# mainboard_rs485_v1_2.net
KiCad netlist of a schematic drawn in Altium Designer
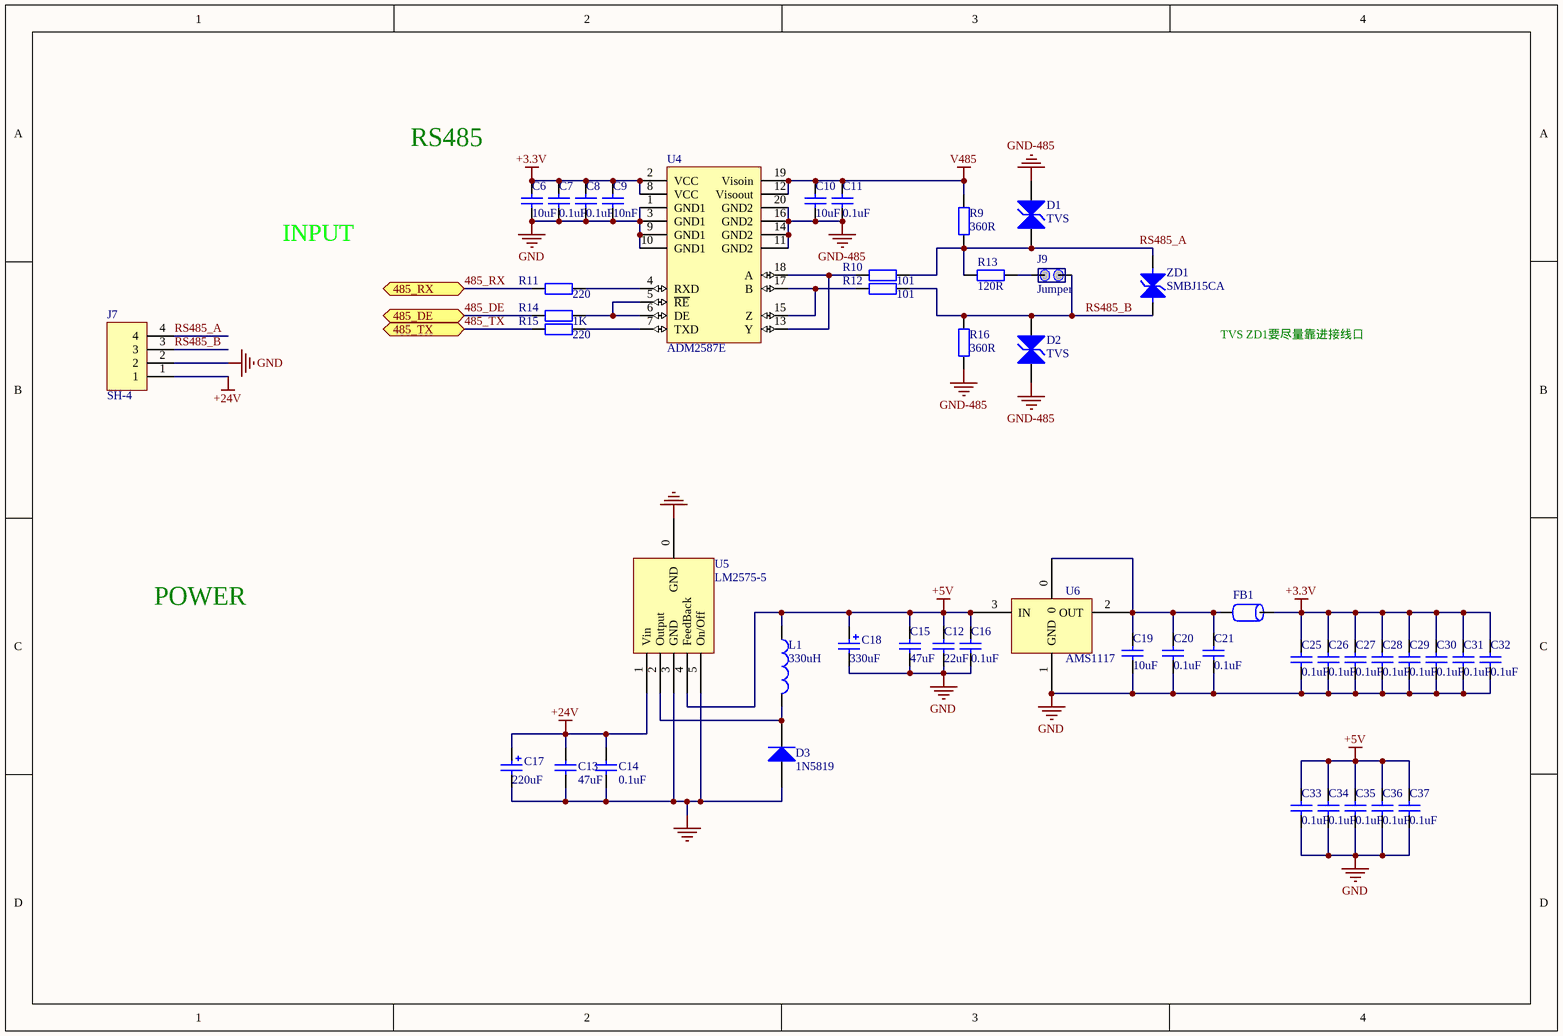
[diagram p0: mainboard_rs485.v1.2.SchDoc]

(export (version "E")
  (design (tool "Eeschema 10.0.6"))
  (components
    (comp (ref "C6")
      (value "10uF")
      (footprint "0805")
      (description "Capacitor")
      (fields (field (name "PUBLISHER") "Altium Limited"))
      (libsource (lib "TIAN's Schlib") (part "Cap"))
    )
    (comp (ref "C7")
      (value "0.1uF")
      (footprint "0805")
      (description "Capacitor")
      (fields (field (name "PUBLISHER") "Altium Limited"))
      (libsource (lib "TIAN's Schlib") (part "Cap"))
    )
    (comp (ref "C8")
      (value "0.1uF")
      (footprint "0805")
      (description "Capacitor")
      (fields (field (name "PUBLISHER") "Altium Limited"))
      (libsource (lib "TIAN's Schlib") (part "Cap"))
    )
    (comp (ref "C9")
      (value "10nF")
      (footprint "0805")
      (description "Capacitor")
      (fields (field (name "PUBLISHER") "Altium Limited"))
      (libsource (lib "TIAN's Schlib") (part "Cap"))
    )
    (comp (ref "C10")
      (value "10uF")
      (footprint "0805")
      (description "Capacitor")
      (fields (field (name "PUBLISHER") "Altium Limited"))
      (libsource (lib "TIAN's Schlib") (part "Cap"))
    )
    (comp (ref "C11")
      (value "0.1uF")
      (footprint "0805")
      (description "Capacitor")
      (fields (field (name "PUBLISHER") "Altium Limited"))
      (libsource (lib "TIAN's Schlib") (part "Cap"))
    )
    (comp (ref "C12") (value "22uF") (footprint "1206") (libsource (lib "Componet") (part "Cap0805")))
    (comp (ref "C13")
      (value "47uF")
      (footprint "1812")
      (description "Capacitor")
      (fields (field (name "PUBLISHER") "Altium Limited"))
      (libsource (lib "Miscellaneous Devices") (part "Cap"))
    )
    (comp (ref "C14")
      (value "0.1uF")
      (footprint "0805")
      (description "Capacitor")
      (fields (field (name "PUBLISHER") "Altium Limited"))
      (libsource (lib "Miscellaneous Devices") (part "Cap"))
    )
    (comp (ref "C15") (value "47uF") (footprint "1812") (libsource (lib "Componet") (part "Cap0805")))
    (comp (ref "C16") (value "0.1uF") (footprint "0805") (libsource (lib "Componet") (part "Cap0805")))
    (comp (ref "C17")
      (value "220uF")
      (footprint "CAP-5mm")
      (description "Polarized Capacitor (Radial)")
      (fields (field (name "PUBLISHER") "Altium Limited"))
      (libsource (lib "Miscellaneous Devices") (part "Cap Pol1"))
    )
    (comp (ref "C18")
      (value "330uF")
      (footprint "CAP-5mm")
      (description "Polarized Capacitor (Radial)")
      (fields (field (name "PUBLISHER") "Altium Limited"))
      (libsource (lib "Miscellaneous Devices") (part "Cap Pol1"))
    )
    (comp (ref "C19") (value "10uF") (footprint "0805") (libsource (lib "Componet") (part "Cap0805")))
    (comp (ref "C20") (value "0.1uF") (footprint "0805") (libsource (lib "Componet") (part "Cap0805")))
    (comp (ref "C21") (value "0.1uF") (footprint "0805") (libsource (lib "Componet") (part "Cap0805")))
    (comp (ref "C25") (value "0.1uF") (footprint "0805") (libsource (lib "Componet") (part "Cap0805")))
    (comp (ref "C26") (value "0.1uF") (footprint "0805") (libsource (lib "Componet") (part "Cap0805")))
    (comp (ref "C27") (value "0.1uF") (footprint "0805") (libsource (lib "Componet") (part "Cap0805")))
    (comp (ref "C28") (value "0.1uF") (footprint "0805") (libsource (lib "Componet") (part "Cap0805")))
    (comp (ref "C29") (value "0.1uF") (footprint "0805") (libsource (lib "Componet") (part "Cap0805")))
    (comp (ref "C30") (value "0.1uF") (footprint "0805") (libsource (lib "Componet") (part "Cap0805")))
    (comp (ref "C31") (value "0.1uF") (footprint "0805") (libsource (lib "Componet") (part "Cap0805")))
    (comp (ref "C32") (value "0.1uF") (footprint "0805") (libsource (lib "Componet") (part "Cap0805")))
    (comp (ref "C33") (value "0.1uF") (footprint "0805") (libsource (lib "Componet") (part "Cap0805")))
    (comp (ref "C34") (value "0.1uF") (footprint "0805") (libsource (lib "Componet") (part "Cap0805")))
    (comp (ref "C35") (value "0.1uF") (footprint "0805") (libsource (lib "Componet") (part "Cap0805")))
    (comp (ref "C36") (value "0.1uF") (footprint "0805") (libsource (lib "Componet") (part "Cap0805")))
    (comp (ref "C37") (value "0.1uF") (footprint "0805") (libsource (lib "Componet") (part "Cap0805")))
    (comp (ref "D1")
      (value "TVS")
      (footprint "SMBJ_DO-214")
      (fields (field (name "PUBLISHER") "Altium Limited"))
      (libsource (lib "TIAN's Schlib") (part "TVS"))
    )
    (comp (ref "D2")
      (value "TVS")
      (footprint "SMBJ_DO-214")
      (fields (field (name "PUBLISHER") "Altium Limited"))
      (libsource (lib "TIAN's Schlib") (part "TVS"))
    )
    (comp (ref "D3")
      (value "1N5819")
      (footprint "Diode_TP2")
      (description "High Conductance Fast Diode")
      (fields (field (name "PUBLISHER") "Altium Limited"))
      (libsource (lib "Miscellaneous Devices") (part "Diode 1N4148"))
    )
    (comp (ref "FB1") (value "FERRITE") (footprint "0805") (libsource (lib "Connector") (part "FERRITE")))
    (comp (ref "J7") (value "SH-4") (footprint "PWR") (libsource (lib "Connector") (part "SH-4")))
    (comp (ref "J9") (value "Jumper") (footprint "J254-2") (libsource (lib "Connector") (part "Jumper")))
    (comp (ref "L1")
      (value "330uH")
      (footprint "Inductance")
      (description "Inductor")
      (fields (field (name "PUBLISHER") "Altium Limited"))
      (libsource (lib "Miscellaneous Devices") (part "Inductor"))
    )
    (comp (ref "R9")
      (value "360R")
      (footprint "0805")
      (description "Resistor")
      (fields (field (name "PUBLISHER") "Altium Limited"))
      (libsource (lib "TIAN's Schlib") (part "Res2"))
    )
    (comp (ref "R10")
      (value "101")
      (footprint "0805")
      (description "Resistor")
      (fields (field (name "PUBLISHER") "Altium Limited"))
      (libsource (lib "") (part "Res2_1"))
    )
    (comp (ref "R11")
      (value "220")
      (footprint "0805")
      (description "Resistor")
      (fields (field (name "PUBLISHER") "Altium Limited"))
      (libsource (lib "TIAN's Schlib") (part "Res2"))
    )
    (comp (ref "R12")
      (value "101")
      (footprint "0805")
      (description "Resistor")
      (fields (field (name "PUBLISHER") "Altium Limited"))
      (libsource (lib "") (part "Res2_1"))
    )
    (comp (ref "R13")
      (value "120R")
      (footprint "0805")
      (description "Resistor")
      (fields (field (name "PUBLISHER") "Altium Limited"))
      (libsource (lib "") (part "Res2_2"))
    )
    (comp (ref "R14")
      (value "1K")
      (footprint "0805")
      (description "Resistor")
      (fields (field (name "PUBLISHER") "Altium Limited"))
      (libsource (lib "TIAN's Schlib") (part "Res2"))
    )
    (comp (ref "R15")
      (value "220")
      (footprint "0805")
      (description "Resistor")
      (fields (field (name "PUBLISHER") "Altium Limited"))
      (libsource (lib "TIAN's Schlib") (part "Res2"))
    )
    (comp (ref "R16")
      (value "360R")
      (footprint "0805")
      (description "Resistor")
      (fields (field (name "PUBLISHER") "Altium Limited"))
      (libsource (lib "TIAN's Schlib") (part "Res2"))
    )
    (comp (ref "U4")
      (value "ADM2587E")
      (footprint "SOIC_W_20")
      (description "isolated DC-DC RS485")
      (libsource (lib "TIAN's Schlib") (part "ADM2587E"))
    )
    (comp (ref "U5") (value "LM2575-5") (footprint "TO-263") (libsource (lib "Leon") (part "LM25XX")))
    (comp (ref "U6") (value "AMS1117") (footprint "TO-223") (libsource (lib "Chip") (part "AMS1117")))
    (comp (ref "ZD1")
      (value "SMBJ15CA")
      (footprint "DO-214AA/SMB")
      (description "瞬态抑制二极管")
      (libsource (lib "ALARM") (part "TVS"))
    )
  )
  (nets
    (net (code "1") (name "+3.3V") (class "Default")
      (node (ref "C25") (pin "2") (pinfunction "2_2") (pintype "passive"))
      (node (ref "C26") (pin "2") (pinfunction "2_2") (pintype "passive"))
      (node (ref "C27") (pin "2") (pinfunction "2_2") (pintype "passive"))
      (node (ref "C28") (pin "2") (pinfunction "2_2") (pintype "passive"))
      (node (ref "C29") (pin "2") (pinfunction "2_2") (pintype "passive"))
      (node (ref "C30") (pin "2") (pinfunction "2_2") (pintype "passive"))
      (node (ref "C31") (pin "2") (pinfunction "2_2") (pintype "passive"))
      (node (ref "C32") (pin "2") (pinfunction "2_2") (pintype "passive"))
      (node (ref "C6") (pin "2") (pinfunction "2_2") (pintype "passive"))
      (node (ref "C7") (pin "2") (pinfunction "2_2") (pintype "passive"))
      (node (ref "C8") (pin "2") (pinfunction "2_2") (pintype "passive"))
      (node (ref "C9") (pin "2") (pinfunction "2_2") (pintype "passive"))
      (node (ref "FB1") (pin "2") (pinfunction "2_2") (pintype "passive"))
      (node (ref "U4") (pin "2") (pinfunction "VCC_2") (pintype "passive"))
      (node (ref "U4") (pin "8") (pinfunction "VCC_8") (pintype "passive"))
    )
    (net (code "2") (name "+5V") (class "Default")
      (node (ref "C12") (pin "2") (pinfunction "2_2") (pintype "passive"))
      (node (ref "C15") (pin "2") (pinfunction "2_2") (pintype "passive"))
      (node (ref "C16") (pin "2") (pinfunction "2_2") (pintype "passive"))
      (node (ref "C18") (pin "1") (pinfunction "1_1") (pintype "passive"))
      (node (ref "C33") (pin "2") (pinfunction "2_2") (pintype "passive"))
      (node (ref "C34") (pin "2") (pinfunction "2_2") (pintype "passive"))
      (node (ref "C35") (pin "2") (pinfunction "2_2") (pintype "passive"))
      (node (ref "C36") (pin "2") (pinfunction "2_2") (pintype "passive"))
      (node (ref "C37") (pin "2") (pinfunction "2_2") (pintype "passive"))
      (node (ref "L1") (pin "1") (pinfunction "1_1") (pintype "passive"))
      (node (ref "U5") (pin "4") (pinfunction "FeedBack_4") (pintype "passive"))
      (node (ref "U6") (pin "3") (pinfunction "IN_3") (pintype "passive"))
    )
    (net (code "3") (name "+24V") (class "Default")
      (node (ref "C13") (pin "2") (pinfunction "2_2") (pintype "passive"))
      (node (ref "C14") (pin "2") (pinfunction "2_2") (pintype "passive"))
      (node (ref "C17") (pin "1") (pinfunction "1_1") (pintype "passive"))
      (node (ref "J7") (pin "1") (pinfunction "1_1") (pintype "passive"))
      (node (ref "U5") (pin "1") (pinfunction "Vin_1") (pintype "passive"))
    )
    (net (code "4") (name "/485_DE") (class "Default")
      (node (ref "R14") (pin "1") (pinfunction "1_1") (pintype "passive"))
    )
    (net (code "5") (name "/485_RX") (class "Default")
      (node (ref "R11") (pin "1") (pinfunction "1_1") (pintype "passive"))
    )
    (net (code "6") (name "/485_TX") (class "Default")
      (node (ref "R15") (pin "1") (pinfunction "1_1") (pintype "passive"))
    )
    (net (code "7") (name "/RS485_A") (class "Default")
      (node (ref "D1") (pin "2") (pinfunction "K_2") (pintype "passive"))
      (node (ref "J7") (pin "4") (pinfunction "4_4") (pintype "passive"))
      (node (ref "R10") (pin "2") (pinfunction "2_2") (pintype "passive"))
      (node (ref "R13") (pin "2") (pinfunction "2_2") (pintype "passive"))
      (node (ref "R9") (pin "1") (pinfunction "1_1") (pintype "passive"))
      (node (ref "ZD1") (pin "1") (pinfunction "1_1") (pintype "passive"))
    )
    (net (code "8") (name "/RS485_B") (class "Default")
      (node (ref "D2") (pin "2") (pinfunction "K_2") (pintype "passive"))
      (node (ref "J7") (pin "3") (pinfunction "3_3") (pintype "passive"))
      (node (ref "J9") (pin "1") (pinfunction "1_1") (pintype "passive"))
      (node (ref "R12") (pin "2") (pinfunction "2_2") (pintype "passive"))
      (node (ref "R16") (pin "2") (pinfunction "2_2") (pintype "passive"))
      (node (ref "ZD1") (pin "2") (pinfunction "2_2") (pintype "passive"))
    )
    (net (code "9") (name "GND") (class "Default")
      (node (ref "C12") (pin "1") (pinfunction "1_1") (pintype "passive"))
      (node (ref "C13") (pin "1") (pinfunction "1_1") (pintype "passive"))
      (node (ref "C14") (pin "1") (pinfunction "1_1") (pintype "passive"))
      (node (ref "C15") (pin "1") (pinfunction "1_1") (pintype "passive"))
      (node (ref "C16") (pin "1") (pinfunction "1_1") (pintype "passive"))
      (node (ref "C17") (pin "2") (pinfunction "2_2") (pintype "passive"))
      (node (ref "C18") (pin "2") (pinfunction "2_2") (pintype "passive"))
      (node (ref "C19") (pin "1") (pinfunction "1_1") (pintype "passive"))
      (node (ref "C20") (pin "1") (pinfunction "1_1") (pintype "passive"))
      (node (ref "C21") (pin "1") (pinfunction "1_1") (pintype "passive"))
      (node (ref "C25") (pin "1") (pinfunction "1_1") (pintype "passive"))
      (node (ref "C26") (pin "1") (pinfunction "1_1") (pintype "passive"))
      (node (ref "C27") (pin "1") (pinfunction "1_1") (pintype "passive"))
      (node (ref "C28") (pin "1") (pinfunction "1_1") (pintype "passive"))
      (node (ref "C29") (pin "1") (pinfunction "1_1") (pintype "passive"))
      (node (ref "C30") (pin "1") (pinfunction "1_1") (pintype "passive"))
      (node (ref "C31") (pin "1") (pinfunction "1_1") (pintype "passive"))
      (node (ref "C32") (pin "1") (pinfunction "1_1") (pintype "passive"))
      (node (ref "C33") (pin "1") (pinfunction "1_1") (pintype "passive"))
      (node (ref "C34") (pin "1") (pinfunction "1_1") (pintype "passive"))
      (node (ref "C35") (pin "1") (pinfunction "1_1") (pintype "passive"))
      (node (ref "C36") (pin "1") (pinfunction "1_1") (pintype "passive"))
      (node (ref "C37") (pin "1") (pinfunction "1_1") (pintype "passive"))
      (node (ref "C6") (pin "1") (pinfunction "1_1") (pintype "passive"))
      (node (ref "C7") (pin "1") (pinfunction "1_1") (pintype "passive"))
      (node (ref "C8") (pin "1") (pinfunction "1_1") (pintype "passive"))
      (node (ref "C9") (pin "1") (pinfunction "1_1") (pintype "passive"))
      (node (ref "D3") (pin "1") (pinfunction "A_1") (pintype "passive"))
      (node (ref "J7") (pin "2") (pinfunction "2_2") (pintype "passive"))
      (node (ref "U4") (pin "1") (pinfunction "GND1_1") (pintype "passive"))
      (node (ref "U4") (pin "10") (pinfunction "GND1_10") (pintype "passive"))
      (node (ref "U4") (pin "3") (pinfunction "GND1_3") (pintype "passive"))
      (node (ref "U4") (pin "9") (pinfunction "GND1_9") (pintype "passive"))
      (node (ref "U5") (pin "0") (pinfunction "GND_0") (pintype "passive"))
      (node (ref "U5") (pin "3") (pinfunction "GND_3") (pintype "passive"))
      (node (ref "U5") (pin "5") (pinfunction "On/Off_5") (pintype "passive"))
      (node (ref "U6") (pin "1") (pinfunction "GND_1") (pintype "passive"))
    )
    (net (code "10") (name "GND-485") (class "Default")
      (node (ref "C10") (pin "1") (pinfunction "1_1") (pintype "passive"))
      (node (ref "C11") (pin "1") (pinfunction "1_1") (pintype "passive"))
      (node (ref "D1") (pin "1") (pinfunction "A_1") (pintype "passive"))
      (node (ref "D2") (pin "1") (pinfunction "A_1") (pintype "passive"))
      (node (ref "R16") (pin "1") (pinfunction "1_1") (pintype "passive"))
      (node (ref "U4") (pin "11") (pinfunction "GND2_11") (pintype "passive"))
      (node (ref "U4") (pin "14") (pinfunction "GND2_14") (pintype "passive"))
      (node (ref "U4") (pin "16") (pinfunction "GND2_16") (pintype "passive"))
      (node (ref "U4") (pin "20") (pinfunction "GND2_20") (pintype "passive"))
    )
    (net (code "11") (name "Net-(D3-K)") (class "Default")
      (node (ref "D3") (pin "2") (pinfunction "K_2") (pintype "passive"))
      (node (ref "L1") (pin "2") (pinfunction "2_2") (pintype "passive"))
      (node (ref "U5") (pin "2") (pinfunction "Output_2") (pintype "passive"))
    )
    (net (code "12") (name "Net-(J9-Pad2)") (class "Default")
      (node (ref "J9") (pin "2") (pinfunction "2_2") (pintype "passive"))
      (node (ref "R13") (pin "1") (pinfunction "1_1") (pintype "passive"))
    )
    (net (code "13") (name "Net-(U4-A)") (class "Default")
      (node (ref "R10") (pin "1") (pinfunction "1_1") (pintype "passive"))
      (node (ref "U4") (pin "13") (pinfunction "Y_13") (pintype "bidirectional"))
      (node (ref "U4") (pin "18") (pinfunction "A_18") (pintype "bidirectional"))
    )
    (net (code "14") (name "Net-(U4-B)") (class "Default")
      (node (ref "R12") (pin "1") (pinfunction "1_1") (pintype "passive"))
      (node (ref "U4") (pin "15") (pinfunction "Z_15") (pintype "bidirectional"))
      (node (ref "U4") (pin "17") (pinfunction "B_17") (pintype "bidirectional"))
    )
    (net (code "15") (name "Net-(U4-DE)") (class "Default")
      (node (ref "R14") (pin "2") (pinfunction "2_2") (pintype "passive"))
      (node (ref "U4") (pin "5") (pinfunction "~{RE}_5") (pintype "bidirectional"))
      (node (ref "U4") (pin "6") (pinfunction "DE_6") (pintype "bidirectional"))
    )
    (net (code "16") (name "Net-(U4-RXD)") (class "Default")
      (node (ref "R11") (pin "2") (pinfunction "2_2") (pintype "passive"))
      (node (ref "U4") (pin "4") (pinfunction "RXD_4") (pintype "bidirectional"))
    )
    (net (code "17") (name "Net-(U4-TXD)") (class "Default")
      (node (ref "R15") (pin "2") (pinfunction "2_2") (pintype "passive"))
      (node (ref "U4") (pin "7") (pinfunction "TXD_7") (pintype "bidirectional"))
    )
    (net (code "18") (name "Net-(U6-OUT)") (class "Default")
      (node (ref "C19") (pin "2") (pinfunction "2_2") (pintype "passive"))
      (node (ref "C20") (pin "2") (pinfunction "2_2") (pintype "passive"))
      (node (ref "C21") (pin "2") (pinfunction "2_2") (pintype "passive"))
      (node (ref "FB1") (pin "1") (pinfunction "1_1") (pintype "passive"))
      (node (ref "U6") (pin "0") (pinfunction "0_0") (pintype "passive"))
      (node (ref "U6") (pin "2") (pinfunction "OUT_2") (pintype "passive"))
    )
    (net (code "19") (name "V485") (class "Default")
      (node (ref "C10") (pin "2") (pinfunction "2_2") (pintype "passive"))
      (node (ref "C11") (pin "2") (pinfunction "2_2") (pintype "passive"))
      (node (ref "R9") (pin "2") (pinfunction "2_2") (pintype "passive"))
      (node (ref "U4") (pin "12") (pinfunction "Visoout_12") (pintype "passive"))
      (node (ref "U4") (pin "19") (pinfunction "Visoin_19") (pintype "passive"))
    )
  )
)
